# Sheet1_1.net
KiCad netlist of a schematic drawn in Altium Designer
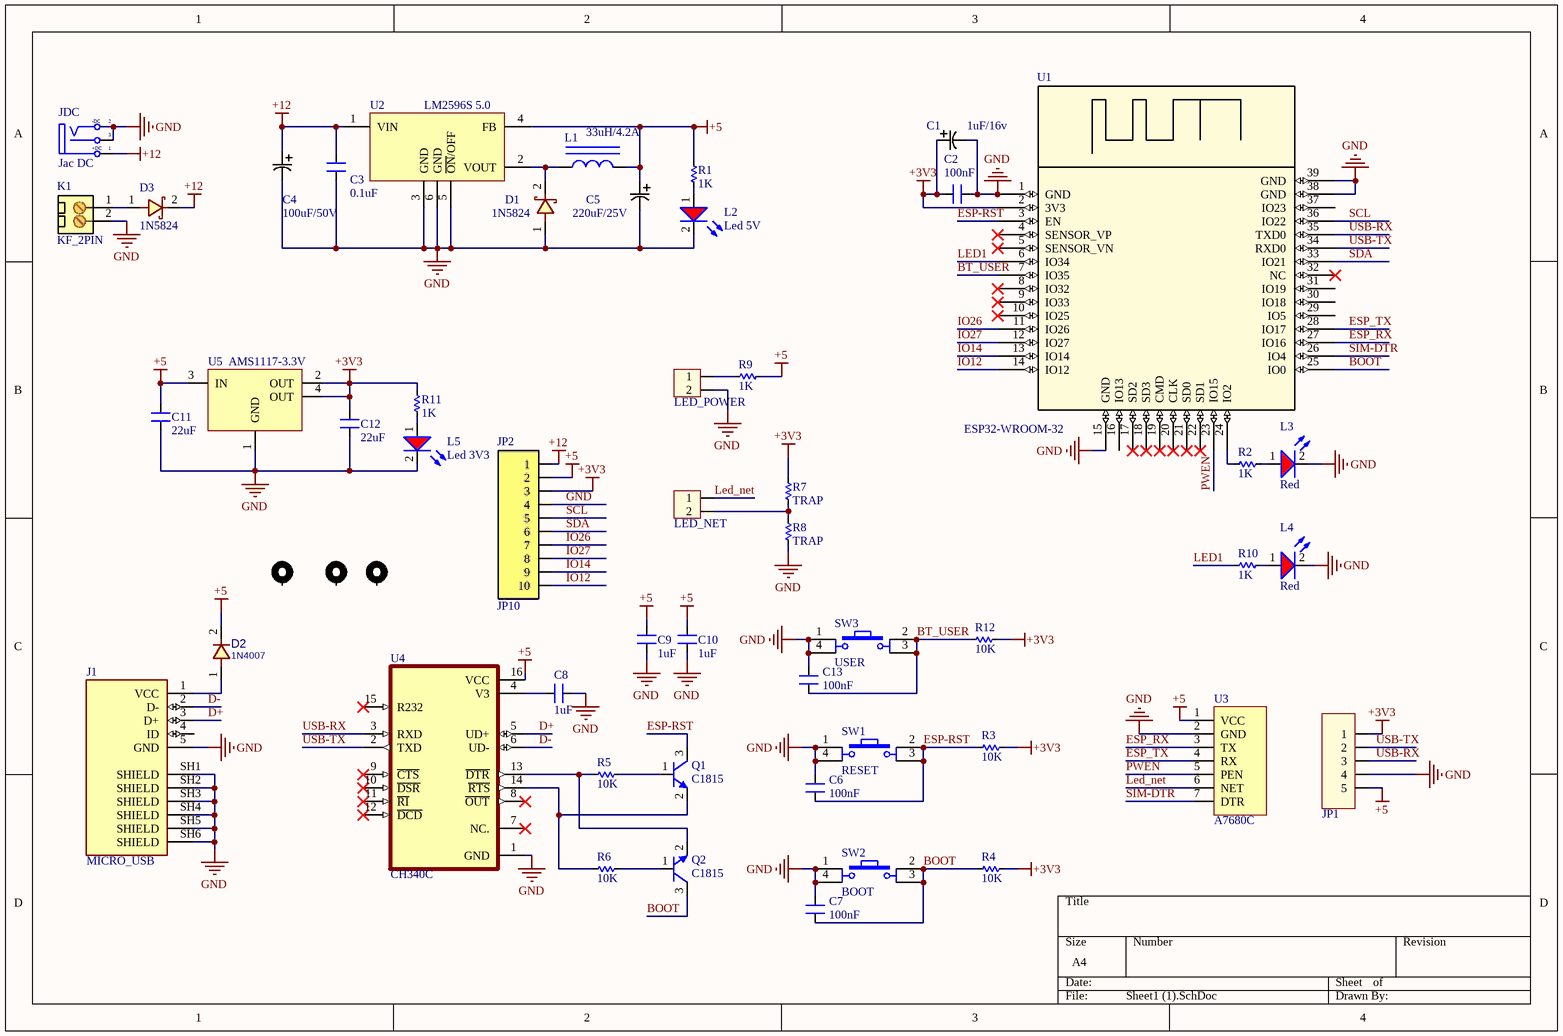
[diagram p0: Sheet1 (1).SchDoc]

(export (version "E")
  (design (tool "Eeschema 10.0.6"))
  (components
    (comp (ref "C1")
      (value "1uF/16v")
      (footprint "CAP-TANTALUM-1206 - ( 3216 )")
      (libsource (lib "") (part "CAP_PHANCUCDEN_1"))
    )
    (comp (ref "C2")
      (value "100nF")
      (footprint "CAP-0603")
      (description "Cap np W0.3")
      (fields (field (name "COPYRIGHT") "VanDungEvn"))
      (libsource (lib "tuananh_smd") (part "CAP ko phan cuc"))
    )
    (comp (ref "C3")
      (value "0.1uF")
      (footprint "CAP-0603")
      (description "Cap np W0.3")
      (fields (field (name "COPYRIGHT") "VanDungEvn"))
      (libsource (lib "tuananh_smd") (part "CAP ko phan cuc"))
    )
    (comp (ref "C4")
      (value "100uF/50V")
      (footprint "C8mm-p3")
      (libsource (lib "Tuấn Anh") (part "CAP_PHANCUCDEN"))
    )
    (comp (ref "C5")
      (value "220uF/25V")
      (footprint "C8mm-p3")
      (libsource (lib "tuananh_smd") (part "CAP_ALU"))
    )
    (comp (ref "C6")
      (value "100nF")
      (footprint "CAP-0603")
      (description "Cap np W0.3")
      (fields (field (name "COPYRIGHT") "VanDungEvn"))
      (libsource (lib "tuananh_smd") (part "CAP ko phan cuc"))
    )
    (comp (ref "C7")
      (value "100nF")
      (footprint "CAP-0603")
      (description "Cap np W0.3")
      (fields (field (name "COPYRIGHT") "VanDungEvn"))
      (libsource (lib "tuananh_smd") (part "CAP ko phan cuc"))
    )
    (comp (ref "C8")
      (value "1uF")
      (footprint "CAP-0603")
      (description "Cap np W0.3")
      (fields (field (name "COPYRIGHT") "VanDungEvn"))
      (libsource (lib "tuananh_smd") (part "CAP ko phan cuc"))
    )
    (comp (ref "C9")
      (value "1uF")
      (footprint "CAP-0603")
      (description "Cap np W0.3")
      (fields (field (name "COPYRIGHT") "VanDungEvn"))
      (libsource (lib "tuananh_smd") (part "CAP ko phan cuc"))
    )
    (comp (ref "C10")
      (value "1uF")
      (footprint "CAP-0603")
      (description "Cap np W0.3")
      (fields (field (name "COPYRIGHT") "VanDungEvn"))
      (libsource (lib "tuananh_smd") (part "CAP ko phan cuc"))
    )
    (comp (ref "C11")
      (value "22uF")
      (footprint "Cap-0805")
      (description "Cap np W0.3")
      (fields (field (name "COPYRIGHT") "VanDungEvn"))
      (libsource (lib "tuananh_smd") (part "CAP ko phan cuc"))
    )
    (comp (ref "C12")
      (value "22uF")
      (footprint "Cap-0805")
      (description "Cap np W0.3")
      (fields (field (name "COPYRIGHT") "VanDungEvn"))
      (libsource (lib "tuananh_smd") (part "CAP ko phan cuc"))
    )
    (comp (ref "C13")
      (value "100nF")
      (footprint "CAP-0603")
      (description "Cap np W0.3")
      (fields (field (name "COPYRIGHT") "VanDungEvn"))
      (libsource (lib "tuananh_smd") (part "CAP ko phan cuc"))
    )
    (comp (ref "D1")
      (value "1N5824")
      (footprint "DO-214AC_SS34")
      (libsource (lib "tuananh_smd") (part "1N5822"))
    )
    (comp (ref "D2")
      (value "1N4007")
      (footprint "SOD-123")
      (description "DIODE, GENERAL PURPOSE, 1000V/1A")
      (fields (field (name "MANF") "Diodes"))
      (libsource (lib "tuananh_smd") (part "DIODE"))
    )
    (comp (ref "D3")
      (value "1N5824")
      (footprint "DO-214AC_SS34")
      (libsource (lib "tuananh_smd") (part "1N5822"))
    )
    (comp (ref "J1")
      (value "MICRO_USB")
      (footprint "MICRO_USB")
      (description "Micro USB, Input Output Connectors, B TYPE RECEPTACLE with flange")
      (fields (field (name "MF") "Amphenol ICC") (field (name "MP") "10118194-0001LF"))
      (libsource (lib "tuananh_smd") (part "MICRO_USB"))
    )
    (comp (ref "JDC")
      (value "Jac DC")
      (footprint "DC-IN_5.5x2.5")
      (description "Jac DC input")
      (libsource (lib "Tuấn Anh") (part "DCIN-DC5525"))
    )
    (comp (ref "JP1") (value "Connector") (footprint "jp5") (libsource (lib "Tuấn Anh") (part "JP5")))
    (comp (ref "JP2")
      (value "JP10")
      (footprint "JP_10PIN")
      (description "Connector 10")
      (libsource (lib "Tuấn Anh") (part "XH2.54_10P"))
    )
    (comp (ref "K1") (value "KF_2PIN") (footprint "KF_2PIN") (libsource (lib "Tuấn Anh") (part "KF_2PIN")))
    (comp (ref "L1")
      (value "33uH/4.2A")
      (footprint "INDC_L127H_331")
      (libsource (lib "Tuấn Anh") (part "inductor"))
    )
    (comp (ref "L2")
      (value "Led 5V")
      (footprint "LED_0805_smd")
      (description "LED Red 3mm/5MM")
      (fields (field (name "Comment") "LED"))
      (libsource (lib "tuananh_smd") (part "LED_RED_SMD"))
    )
    (comp (ref "L3")
      (value "Red")
      (footprint "LED_0805_smd")
      (description "LED Red 3mm/5MM")
      (fields (field (name "Comment") "LED"))
      (libsource (lib "tuananh_smd") (part "LED_RED_SMD"))
    )
    (comp (ref "L4")
      (value "Red")
      (footprint "LED_0805_smd")
      (description "LED Red 3mm/5MM")
      (fields (field (name "Comment") "LED"))
      (libsource (lib "tuananh_smd") (part "LED_RED_SMD"))
    )
    (comp (ref "L5")
      (value "Led 3V3")
      (footprint "LED_0805_smd")
      (description "LED Red 3mm/5MM")
      (fields (field (name "Comment") "LED"))
      (libsource (lib "tuananh_smd") (part "LED_RED_SMD"))
    )
    (comp (ref "LED_NET")
      (value "BUS_2PIN")
      (footprint "CON2")
      (description "Connector 2")
      (libsource (lib "Tuấn Anh") (part "CON2"))
    )
    (comp (ref "LED_POWER")
      (value "BUS_2PIN")
      (footprint "CON2")
      (description "Connector 2")
      (libsource (lib "Tuấn Anh") (part "CON2"))
    )
    (comp (ref "Q1")
      (value "C1815")
      (footprint "SOT-23")
      (description "Trans NPN 50V 150mA TO-92")
      (libsource (lib "tuananh_smd") (part "C1815-SMD"))
    )
    (comp (ref "Q2")
      (value "C1815")
      (footprint "SOT-23")
      (description "Trans NPN 50V 150mA TO-92")
      (libsource (lib "tuananh_smd") (part "C1815-SMD"))
    )
    (comp (ref "R1")
      (value "1K")
      (footprint "RES-0603")
      (description "Res")
      (fields
        (field (name "MANUFACTURER") "Generic Components")
        (field (name "PUBLISHER") "Altium Hobart Technology Centre")
      )
      (libsource (lib "tuananh_smd") (part "Res"))
    )
    (comp (ref "R2")
      (value "1K")
      (footprint "RES-0603")
      (description "Res")
      (fields
        (field (name "MANUFACTURER") "Generic Components")
        (field (name "PUBLISHER") "Altium Hobart Technology Centre")
      )
      (libsource (lib "tuananh_smd") (part "Res"))
    )
    (comp (ref "R3")
      (value "10K")
      (footprint "RES-0603")
      (description "Res")
      (fields
        (field (name "MANUFACTURER") "Generic Components")
        (field (name "PUBLISHER") "Altium Hobart Technology Centre")
      )
      (libsource (lib "Tuấn Anh") (part "Res"))
    )
    (comp (ref "R4")
      (value "10K")
      (footprint "RES-0603")
      (description "Res")
      (fields
        (field (name "MANUFACTURER") "Generic Components")
        (field (name "PUBLISHER") "Altium Hobart Technology Centre")
      )
      (libsource (lib "Tuấn Anh") (part "Res"))
    )
    (comp (ref "R5")
      (value "10K")
      (footprint "RES-0603")
      (description "Res")
      (fields
        (field (name "MANUFACTURER") "Generic Components")
        (field (name "PUBLISHER") "Altium Hobart Technology Centre")
      )
      (libsource (lib "Tuấn Anh") (part "Res"))
    )
    (comp (ref "R6")
      (value "10K")
      (footprint "RES-0603")
      (description "Res")
      (fields
        (field (name "MANUFACTURER") "Generic Components")
        (field (name "PUBLISHER") "Altium Hobart Technology Centre")
      )
      (libsource (lib "Tuấn Anh") (part "Res"))
    )
    (comp (ref "R7")
      (value "TRAP")
      (footprint "RES-0603")
      (description "Res")
      (fields
        (field (name "MANUFACTURER") "Generic Components")
        (field (name "PUBLISHER") "Altium Hobart Technology Centre")
      )
      (libsource (lib "tuananh_smd") (part "Res"))
    )
    (comp (ref "R8")
      (value "TRAP")
      (footprint "RES-0603")
      (description "Res")
      (fields
        (field (name "MANUFACTURER") "Generic Components")
        (field (name "PUBLISHER") "Altium Hobart Technology Centre")
      )
      (libsource (lib "tuananh_smd") (part "Res"))
    )
    (comp (ref "R9")
      (value "1K")
      (footprint "RES-0603")
      (description "Res")
      (fields
        (field (name "MANUFACTURER") "Generic Components")
        (field (name "PUBLISHER") "Altium Hobart Technology Centre")
      )
      (libsource (lib "tuananh_smd") (part "Res"))
    )
    (comp (ref "R10")
      (value "1K")
      (footprint "RES-0603")
      (description "Res")
      (fields
        (field (name "MANUFACTURER") "Generic Components")
        (field (name "PUBLISHER") "Altium Hobart Technology Centre")
      )
      (libsource (lib "tuananh_smd") (part "Res"))
    )
    (comp (ref "R11")
      (value "1K")
      (footprint "RES-0603")
      (description "Res")
      (fields
        (field (name "MANUFACTURER") "Generic Components")
        (field (name "PUBLISHER") "Altium Hobart Technology Centre")
      )
      (libsource (lib "tuananh_smd") (part "Res"))
    )
    (comp (ref "R12")
      (value "10K")
      (footprint "RES-0603")
      (description "Res")
      (fields
        (field (name "MANUFACTURER") "Generic Components")
        (field (name "PUBLISHER") "Altium Hobart Technology Centre")
      )
      (libsource (lib "Tuấn Anh") (part "Res"))
    )
    (comp (ref "SW1")
      (value "RESET")
      (footprint "SW4-SMD-6mm")
      (libsource (lib "tuananh_smd") (part "Button"))
    )
    (comp (ref "SW2")
      (value "BOOT")
      (footprint "SW4-SMD-6mm")
      (libsource (lib "tuananh_smd") (part "Button"))
    )
    (comp (ref "SW3")
      (value "USER")
      (footprint "SW4-SMD-6mm")
      (libsource (lib "tuananh_smd") (part "Button"))
    )
    (comp (ref "U1")
      (value "ESP32-WROOM-32")
      (footprint "ESP32-WROOM-32D")
      (libsource (lib "tuananh_smd") (part "ESP32-WROOM-32"))
    )
    (comp (ref "U2")
      (value "LM2596S 5.0")
      (footprint "TO263-5")
      (description "1A Regulator")
      (libsource (lib "Tuấn Anh") (part "LM2596"))
    )
    (comp (ref "U3")
      (value "A7680C")
      (footprint "TDM-SIM7680C-POWER_LOGIC")
      (libsource (lib "tuananh_smd") (part "SIMCOM_A7680C_MODULE"))
    )
    (comp (ref "U4") (value "CH340C") (footprint "SOP-16") (libsource (lib "tuananh_smd") (part "CH340C")))
    (comp (ref "U5")
      (value "AMS1117-3.3V")
      (footprint "SOT223-4M")
      (libsource (lib "tuananh_smd") (part "AMS1117"))
    )
    (comp (ref "V1") (value "VIA") (footprint "VIA") (libsource (lib "Tuấn Anh") (part "VIA")))
    (comp (ref "V2") (value "VIA") (footprint "VIA") (libsource (lib "Tuấn Anh") (part "VIA")))
    (comp (ref "V3") (value "VIA") (footprint "VIA") (libsource (lib "Tuấn Anh") (part "VIA")))
  )
  (nets
    (net (code "1") (name "+3V3") (class "Default")
      (node (ref "C1") (pin "1") (pinfunction "1_1") (pintype "passive"))
      (node (ref "C12") (pin "1") (pinfunction "1_1") (pintype "passive"))
      (node (ref "C2") (pin "1") (pinfunction "1_1") (pintype "passive"))
      (node (ref "JP1") (pin "1") (pinfunction "1_1") (pintype "passive"))
      (node (ref "JP2") (pin "3") (pinfunction "3_3") (pintype "passive"))
      (node (ref "R11") (pin "1") (pinfunction "1_1") (pintype "passive"))
      (node (ref "R12") (pin "2") (pinfunction "2_2") (pintype "passive"))
      (node (ref "R3") (pin "2") (pinfunction "2_2") (pintype "passive"))
      (node (ref "R4") (pin "2") (pinfunction "2_2") (pintype "passive"))
      (node (ref "R7") (pin "2") (pinfunction "2_2") (pintype "passive"))
      (node (ref "U1") (pin "2") (pinfunction "3V3_2") (pintype "bidirectional"))
      (node (ref "U5") (pin "2") (pinfunction "OUT_2") (pintype "passive"))
      (node (ref "U5") (pin "4") (pinfunction "OUT_4") (pintype "passive"))
    )
    (net (code "2") (name "+5") (class "Default")
      (node (ref "C10") (pin "2") (pinfunction "2_2") (pintype "passive"))
      (node (ref "C11") (pin "1") (pinfunction "1_1") (pintype "passive"))
      (node (ref "C5") (pin "1") (pinfunction "1_1") (pintype "passive"))
      (node (ref "C9") (pin "2") (pinfunction "2_2") (pintype "passive"))
      (node (ref "D2") (pin "2") (pinfunction "2_2") (pintype "passive"))
      (node (ref "JP1") (pin "5") (pinfunction "5_5") (pintype "passive"))
      (node (ref "JP2") (pin "2") (pinfunction "2_2") (pintype "passive"))
      (node (ref "L1") (pin "2") (pinfunction "2_2") (pintype "passive"))
      (node (ref "R1") (pin "1") (pinfunction "1_1") (pintype "passive"))
      (node (ref "R9") (pin "1") (pinfunction "1_1") (pintype "passive"))
      (node (ref "U2") (pin "4") (pinfunction "FB_4") (pintype "passive"))
      (node (ref "U3") (pin "1") (pinfunction "VCC_1") (pintype "passive"))
      (node (ref "U4") (pin "16") (pinfunction "VCC_16") (pintype "power_in"))
      (node (ref "U5") (pin "3") (pinfunction "IN_3") (pintype "passive"))
    )
    (net (code "3") (name "+12") (class "Default")
      (node (ref "C3") (pin "2") (pinfunction "2_2") (pintype "passive"))
      (node (ref "C4") (pin "1") (pinfunction "1_1") (pintype "passive"))
      (node (ref "D3") (pin "2") (pinfunction "2_2") (pintype "passive"))
      (node (ref "JDC") (pin "1") (pinfunction "T_1") (pintype "passive"))
      (node (ref "JP2") (pin "1") (pinfunction "1_1") (pintype "passive"))
      (node (ref "U2") (pin "1") (pinfunction "VIN_1") (pintype "passive"))
    )
    (net (code "4") (name "/BOOT") (class "Default")
      (node (ref "C7") (pin "2") (pinfunction "2_2") (pintype "passive"))
      (node (ref "Q2") (pin "3") (pinfunction "C_3") (pintype "passive"))
      (node (ref "R4") (pin "1") (pinfunction "1_1") (pintype "passive"))
      (node (ref "SW2") (pin "2") (pintype "passive"))
      (node (ref "SW2") (pin "3") (pintype "passive"))
      (node (ref "U1") (pin "25") (pinfunction "IO0_25") (pintype "bidirectional"))
    )
    (net (code "5") (name "/BT_USER") (class "Default")
      (node (ref "C13") (pin "2") (pinfunction "2_2") (pintype "passive"))
      (node (ref "R12") (pin "1") (pinfunction "1_1") (pintype "passive"))
      (node (ref "SW3") (pin "2") (pintype "passive"))
      (node (ref "SW3") (pin "3") (pintype "passive"))
      (node (ref "U1") (pin "7") (pinfunction "IO35_7") (pintype "bidirectional"))
    )
    (net (code "6") (name "/D+") (class "Default")
      (node (ref "J1") (pin "3") (pinfunction "D+_3") (pintype "bidirectional"))
      (node (ref "U4") (pin "5") (pinfunction "UD+_5") (pintype "bidirectional"))
    )
    (net (code "7") (name "/D-") (class "Default")
      (node (ref "J1") (pin "2") (pinfunction "D-_2") (pintype "bidirectional"))
      (node (ref "U4") (pin "6") (pinfunction "UD-_6") (pintype "bidirectional"))
    )
    (net (code "8") (name "/ESP-RST") (class "Default")
      (node (ref "C6") (pin "2") (pinfunction "2_2") (pintype "passive"))
      (node (ref "Q1") (pin "3") (pinfunction "C_3") (pintype "passive"))
      (node (ref "R3") (pin "1") (pinfunction "1_1") (pintype "passive"))
      (node (ref "SW1") (pin "2") (pintype "passive"))
      (node (ref "SW1") (pin "3") (pintype "passive"))
      (node (ref "U1") (pin "3") (pinfunction "EN_3") (pintype "bidirectional"))
    )
    (net (code "9") (name "/ESP_RX") (class "Default")
      (node (ref "U1") (pin "27") (pinfunction "IO16_27") (pintype "bidirectional"))
      (node (ref "U3") (pin "3") (pinfunction "TX_3") (pintype "passive"))
    )
    (net (code "10") (name "/ESP_TX") (class "Default")
      (node (ref "U1") (pin "28") (pinfunction "IO17_28") (pintype "bidirectional"))
      (node (ref "U3") (pin "4") (pinfunction "RX_4") (pintype "passive"))
    )
    (net (code "11") (name "/IO12") (class "Default")
      (node (ref "JP2") (pin "10") (pinfunction "10_10") (pintype "passive"))
      (node (ref "U1") (pin "14") (pinfunction "IO12_14") (pintype "bidirectional"))
    )
    (net (code "12") (name "/IO14") (class "Default")
      (node (ref "JP2") (pin "9") (pinfunction "9_9") (pintype "passive"))
      (node (ref "U1") (pin "13") (pinfunction "IO14_13") (pintype "bidirectional"))
    )
    (net (code "13") (name "/IO26") (class "Default")
      (node (ref "JP2") (pin "7") (pinfunction "7_7") (pintype "passive"))
      (node (ref "U1") (pin "11") (pinfunction "IO26_11") (pintype "bidirectional"))
    )
    (net (code "14") (name "/IO27") (class "Default")
      (node (ref "JP2") (pin "8") (pinfunction "8_8") (pintype "passive"))
      (node (ref "U1") (pin "12") (pinfunction "IO27_12") (pintype "bidirectional"))
    )
    (net (code "15") (name "/LED1") (class "Default")
      (node (ref "R10") (pin "1") (pinfunction "1_1") (pintype "passive"))
      (node (ref "U1") (pin "6") (pinfunction "IO34_6") (pintype "bidirectional"))
    )
    (net (code "16") (name "/Led_net") (class "Default")
      (node (ref "LED_NET") (pin "1") (pinfunction "1_1") (pintype "passive"))
      (node (ref "U3") (pin "6") (pinfunction "NET_6") (pintype "passive"))
    )
    (net (code "17") (name "/PWEN") (class "Default")
      (node (ref "U1") (pin "23") (pinfunction "IO15_23") (pintype "bidirectional"))
      (node (ref "U3") (pin "5") (pinfunction "PEN_5") (pintype "passive"))
    )
    (net (code "18") (name "/SCL") (class "Default")
      (node (ref "JP2") (pin "5") (pinfunction "5_5") (pintype "passive"))
      (node (ref "U1") (pin "36") (pinfunction "IO22_36") (pintype "bidirectional"))
    )
    (net (code "19") (name "/SDA") (class "Default")
      (node (ref "JP2") (pin "6") (pinfunction "6_6") (pintype "passive"))
      (node (ref "U1") (pin "33") (pinfunction "IO21_33") (pintype "bidirectional"))
    )
    (net (code "20") (name "/SIM-DTR") (class "Default")
      (node (ref "U1") (pin "26") (pinfunction "IO4_26") (pintype "bidirectional"))
      (node (ref "U3") (pin "7") (pinfunction "DTR_7") (pintype "passive"))
    )
    (net (code "21") (name "/USB-RX") (class "Default")
      (node (ref "JP1") (pin "3") (pinfunction "3_3") (pintype "passive"))
      (node (ref "U1") (pin "35") (pinfunction "TXD0_35") (pintype "bidirectional"))
      (node (ref "U4") (pin "3") (pinfunction "RXD_3") (pintype "input"))
    )
    (net (code "22") (name "/USB-TX") (class "Default")
      (node (ref "JP1") (pin "2") (pinfunction "2_2") (pintype "passive"))
      (node (ref "U1") (pin "34") (pinfunction "RXD0_34") (pintype "bidirectional"))
      (node (ref "U4") (pin "2") (pinfunction "TXD_2") (pintype "output"))
    )
    (net (code "23") (name "GND") (class "Default")
      (node (ref "C1") (pin "2") (pinfunction "2_2") (pintype "passive"))
      (node (ref "C10") (pin "1") (pinfunction "1_1") (pintype "passive"))
      (node (ref "C11") (pin "2") (pinfunction "2_2") (pintype "passive"))
      (node (ref "C12") (pin "2") (pinfunction "2_2") (pintype "passive"))
      (node (ref "C13") (pin "1") (pinfunction "1_1") (pintype "passive"))
      (node (ref "C2") (pin "2") (pinfunction "2_2") (pintype "passive"))
      (node (ref "C3") (pin "1") (pinfunction "1_1") (pintype "passive"))
      (node (ref "C4") (pin "2") (pinfunction "2_2") (pintype "passive"))
      (node (ref "C5") (pin "2") (pinfunction "2_2") (pintype "passive"))
      (node (ref "C6") (pin "1") (pinfunction "1_1") (pintype "passive"))
      (node (ref "C7") (pin "1") (pinfunction "1_1") (pintype "passive"))
      (node (ref "C8") (pin "2") (pinfunction "2_2") (pintype "passive"))
      (node (ref "C9") (pin "1") (pinfunction "1_1") (pintype "passive"))
      (node (ref "D1") (pin "1") (pinfunction "1_1") (pintype "passive"))
      (node (ref "J1") (pin "5") (pinfunction "GND_5") (pintype "power_in"))
      (node (ref "J1") (pin "SH1") (pinfunction "SHIELD_SH1") (pintype "passive"))
      (node (ref "J1") (pin "SH2") (pinfunction "SHIELD_SH2") (pintype "passive"))
      (node (ref "J1") (pin "SH3") (pinfunction "SHIELD_SH3") (pintype "passive"))
      (node (ref "J1") (pin "SH4") (pinfunction "SHIELD_SH4") (pintype "passive"))
      (node (ref "J1") (pin "SH5") (pinfunction "SHIELD_SH5") (pintype "passive"))
      (node (ref "J1") (pin "SH6") (pinfunction "SHIELD_SH6") (pintype "passive"))
      (node (ref "JDC") (pin "2") (pinfunction "TN_2") (pintype "passive"))
      (node (ref "JDC") (pin "3") (pinfunction "S_3") (pintype "power_in"))
      (node (ref "JP1") (pin "4") (pinfunction "4_4") (pintype "passive"))
      (node (ref "JP2") (pin "4") (pinfunction "4_4") (pintype "passive"))
      (node (ref "K1") (pin "2") (pinfunction "2_2") (pintype "passive"))
      (node (ref "L2") (pin "2") (pinfunction "K_2") (pintype "passive"))
      (node (ref "L3") (pin "2") (pinfunction "K_2") (pintype "passive"))
      (node (ref "L4") (pin "2") (pinfunction "K_2") (pintype "passive"))
      (node (ref "L5") (pin "2") (pinfunction "K_2") (pintype "passive"))
      (node (ref "LED_POWER") (pin "2") (pinfunction "2_2") (pintype "passive"))
      (node (ref "R8") (pin "1") (pinfunction "1_1") (pintype "passive"))
      (node (ref "SW1") (pin "1") (pintype "passive"))
      (node (ref "SW1") (pin "4") (pintype "passive"))
      (node (ref "SW2") (pin "1") (pintype "passive"))
      (node (ref "SW2") (pin "4") (pintype "passive"))
      (node (ref "SW3") (pin "1") (pintype "passive"))
      (node (ref "SW3") (pin "4") (pintype "passive"))
      (node (ref "U1") (pin "1") (pinfunction "GND_1") (pintype "bidirectional"))
      (node (ref "U1") (pin "15") (pinfunction "GND_15") (pintype "bidirectional"))
      (node (ref "U1") (pin "38") (pinfunction "GND_38") (pintype "bidirectional"))
      (node (ref "U1") (pin "39") (pinfunction "GND_39") (pintype "bidirectional"))
      (node (ref "U2") (pin "3") (pinfunction "GND_3") (pintype "passive"))
      (node (ref "U2") (pin "5") (pinfunction "~{ON}/OFF_5") (pintype "passive"))
      (node (ref "U2") (pin "6") (pinfunction "GND_6") (pintype "passive"))
      (node (ref "U3") (pin "2") (pinfunction "GND_2") (pintype "passive"))
      (node (ref "U4") (pin "1") (pinfunction "GND_1") (pintype "power_in"))
      (node (ref "U5") (pin "1") (pinfunction "GND_1") (pintype "passive"))
    )
    (net (code "24") (name "Net-(D3-Pad1)") (class "Default")
      (node (ref "D3") (pin "1") (pinfunction "1_1") (pintype "passive"))
      (node (ref "K1") (pin "1") (pinfunction "1_1") (pintype "passive"))
    )
    (net (code "25") (name "Net-(J1-VCC)") (class "Default")
      (node (ref "D2") (pin "1") (pinfunction "1_1") (pintype "passive"))
      (node (ref "J1") (pin "1") (pinfunction "VCC_1") (pintype "power_in"))
    )
    (net (code "26") (name "Net-(L2-A)") (class "Default")
      (node (ref "L2") (pin "1") (pinfunction "A_1") (pintype "passive"))
      (node (ref "R1") (pin "2") (pinfunction "2_2") (pintype "passive"))
    )
    (net (code "27") (name "Net-(L3-A)") (class "Default")
      (node (ref "L3") (pin "1") (pinfunction "A_1") (pintype "passive"))
      (node (ref "R2") (pin "2") (pinfunction "2_2") (pintype "passive"))
    )
    (net (code "28") (name "Net-(L4-A)") (class "Default")
      (node (ref "L4") (pin "1") (pinfunction "A_1") (pintype "passive"))
      (node (ref "R10") (pin "2") (pinfunction "2_2") (pintype "passive"))
    )
    (net (code "29") (name "Net-(L5-A)") (class "Default")
      (node (ref "L5") (pin "1") (pinfunction "A_1") (pintype "passive"))
      (node (ref "R11") (pin "2") (pinfunction "2_2") (pintype "passive"))
    )
    (net (code "30") (name "Net-(LED_NET-Pad2)") (class "Default")
      (node (ref "LED_NET") (pin "2") (pinfunction "2_2") (pintype "passive"))
      (node (ref "R7") (pin "1") (pinfunction "1_1") (pintype "passive"))
      (node (ref "R8") (pin "2") (pinfunction "2_2") (pintype "passive"))
    )
    (net (code "31") (name "Net-(LED_POWER-Pad1)") (class "Default")
      (node (ref "LED_POWER") (pin "1") (pinfunction "1_1") (pintype "passive"))
      (node (ref "R9") (pin "2") (pinfunction "2_2") (pintype "passive"))
    )
    (net (code "32") (name "Net-(Q1-B)") (class "Default")
      (node (ref "Q1") (pin "1") (pinfunction "B_1") (pintype "passive"))
      (node (ref "R5") (pin "2") (pinfunction "2_2") (pintype "passive"))
    )
    (net (code "33") (name "Net-(Q1-E)") (class "Default")
      (node (ref "Q1") (pin "2") (pinfunction "E_2") (pintype "passive"))
      (node (ref "R6") (pin "1") (pinfunction "1_1") (pintype "passive"))
      (node (ref "U4") (pin "14") (pinfunction "~{RTS}_14") (pintype "output"))
    )
    (net (code "34") (name "Net-(Q2-B)") (class "Default")
      (node (ref "Q2") (pin "1") (pinfunction "B_1") (pintype "passive"))
      (node (ref "R6") (pin "2") (pinfunction "2_2") (pintype "passive"))
    )
    (net (code "35") (name "Net-(Q2-E)") (class "Default")
      (node (ref "Q2") (pin "2") (pinfunction "E_2") (pintype "passive"))
      (node (ref "R5") (pin "1") (pinfunction "1_1") (pintype "passive"))
      (node (ref "U4") (pin "13") (pinfunction "~{DTR}_13") (pintype "output"))
    )
    (net (code "36") (name "Net-(U1-IO2)") (class "Default")
      (node (ref "R2") (pin "1") (pinfunction "1_1") (pintype "passive"))
      (node (ref "U1") (pin "24") (pinfunction "IO2_24") (pintype "bidirectional"))
    )
    (net (code "37") (name "Net-(U2-VOUT)") (class "Default")
      (node (ref "D1") (pin "2") (pinfunction "2_2") (pintype "passive"))
      (node (ref "L1") (pin "1") (pinfunction "1_1") (pintype "passive"))
      (node (ref "U2") (pin "2") (pinfunction "VOUT_2") (pintype "passive"))
    )
    (net (code "38") (name "Net-(U4-V3)") (class "Default")
      (node (ref "C8") (pin "1") (pinfunction "1_1") (pintype "passive"))
      (node (ref "U4") (pin "4") (pinfunction "V3_4") (pintype "power_in"))
    )
    (net (code "39") (name "unconnected-(J1-ID-Pad4)") (class "Default")
      (node (ref "J1") (pin "4") (pinfunction "ID_4") (pintype "bidirectional"))
    )
    (net (code "40") (name "unconnected-(U1-CLK-Pad20)") (class "Default")
      (node (ref "U1") (pin "20") (pinfunction "CLK_20") (pintype "bidirectional+no_connect"))
    )
    (net (code "41") (name "unconnected-(U1-CMD-Pad19)") (class "Default")
      (node (ref "U1") (pin "19") (pinfunction "CMD_19") (pintype "bidirectional+no_connect"))
    )
    (net (code "42") (name "unconnected-(U1-IO5-Pad29)") (class "Default")
      (node (ref "U1") (pin "29") (pinfunction "IO5_29") (pintype "bidirectional"))
    )
    (net (code "43") (name "unconnected-(U1-IO13-Pad16)") (class "Default")
      (node (ref "U1") (pin "16") (pinfunction "IO13_16") (pintype "bidirectional"))
    )
    (net (code "44") (name "unconnected-(U1-IO18-Pad30)") (class "Default")
      (node (ref "U1") (pin "30") (pinfunction "IO18_30") (pintype "bidirectional"))
    )
    (net (code "45") (name "unconnected-(U1-IO19-Pad31)") (class "Default")
      (node (ref "U1") (pin "31") (pinfunction "IO19_31") (pintype "bidirectional"))
    )
    (net (code "46") (name "unconnected-(U1-IO23-Pad37)") (class "Default")
      (node (ref "U1") (pin "37") (pinfunction "IO23_37") (pintype "bidirectional"))
    )
    (net (code "47") (name "unconnected-(U1-IO25-Pad10)") (class "Default")
      (node (ref "U1") (pin "10") (pinfunction "IO25_10") (pintype "bidirectional+no_connect"))
    )
    (net (code "48") (name "unconnected-(U1-IO32-Pad8)") (class "Default")
      (node (ref "U1") (pin "8") (pinfunction "IO32_8") (pintype "bidirectional+no_connect"))
    )
    (net (code "49") (name "unconnected-(U1-IO33-Pad9)") (class "Default")
      (node (ref "U1") (pin "9") (pinfunction "IO33_9") (pintype "bidirectional+no_connect"))
    )
    (net (code "50") (name "unconnected-(U1-NC-Pad32)") (class "Default")
      (node (ref "U1") (pin "32") (pinfunction "NC_32") (pintype "bidirectional+no_connect"))
    )
    (net (code "51") (name "unconnected-(U1-SD0-Pad21)") (class "Default")
      (node (ref "U1") (pin "21") (pinfunction "SD0_21") (pintype "bidirectional+no_connect"))
    )
    (net (code "52") (name "unconnected-(U1-SD1-Pad22)") (class "Default")
      (node (ref "U1") (pin "22") (pinfunction "SD1_22") (pintype "bidirectional+no_connect"))
    )
    (net (code "53") (name "unconnected-(U1-SD2-Pad17)") (class "Default")
      (node (ref "U1") (pin "17") (pinfunction "SD2_17") (pintype "bidirectional+no_connect"))
    )
    (net (code "54") (name "unconnected-(U1-SD3-Pad18)") (class "Default")
      (node (ref "U1") (pin "18") (pinfunction "SD3_18") (pintype "bidirectional+no_connect"))
    )
    (net (code "55") (name "unconnected-(U1-SENSOR_VN-Pad5)") (class "Default")
      (node (ref "U1") (pin "5") (pinfunction "SENSOR_VN_5") (pintype "bidirectional+no_connect"))
    )
    (net (code "56") (name "unconnected-(U1-SENSOR_VP-Pad4)") (class "Default")
      (node (ref "U1") (pin "4") (pinfunction "SENSOR_VP_4") (pintype "bidirectional+no_connect"))
    )
    (net (code "57") (name "unconnected-(U4-NC.-Pad7)") (class "Default")
      (node (ref "U4") (pin "7") (pinfunction "NC._7") (pintype "passive+no_connect"))
    )
    (net (code "58") (name "unconnected-(U4-R232-Pad15)") (class "Default")
      (node (ref "U4") (pin "15") (pinfunction "R232_15") (pintype "input+no_connect"))
    )
    (net (code "59") (name "unconnected-(U4-~{CTS}-Pad9)") (class "Default")
      (node (ref "U4") (pin "9") (pinfunction "~{CTS}_9") (pintype "input+no_connect"))
    )
    (net (code "60") (name "unconnected-(U4-~{DCD}-Pad12)") (class "Default")
      (node (ref "U4") (pin "12") (pinfunction "~{DCD}_12") (pintype "input+no_connect"))
    )
    (net (code "61") (name "unconnected-(U4-~{DSR}-Pad10)") (class "Default")
      (node (ref "U4") (pin "10") (pinfunction "~{DSR}_10") (pintype "input+no_connect"))
    )
    (net (code "62") (name "unconnected-(U4-~{OUT}-Pad8)") (class "Default")
      (node (ref "U4") (pin "8") (pinfunction "~{OUT}_8") (pintype "output+no_connect"))
    )
    (net (code "63") (name "unconnected-(U4-~{RI}-Pad11)") (class "Default")
      (node (ref "U4") (pin "11") (pinfunction "~{RI}_11") (pintype "input+no_connect"))
    )
    (net (code "64") (name "unconnected-(V1-Pad1)") (class "Default")
      (node (ref "V1") (pin "1") (pinfunction "1_1") (pintype "passive"))
    )
    (net (code "65") (name "unconnected-(V2-Pad1)") (class "Default")
      (node (ref "V2") (pin "1") (pinfunction "1_1") (pintype "passive"))
    )
    (net (code "66") (name "unconnected-(V3-Pad1)") (class "Default")
      (node (ref "V3") (pin "1") (pinfunction "1_1") (pintype "passive"))
    )
  )
)
